# Power.net
KiCad netlist of a schematic drawn in Altium Designer
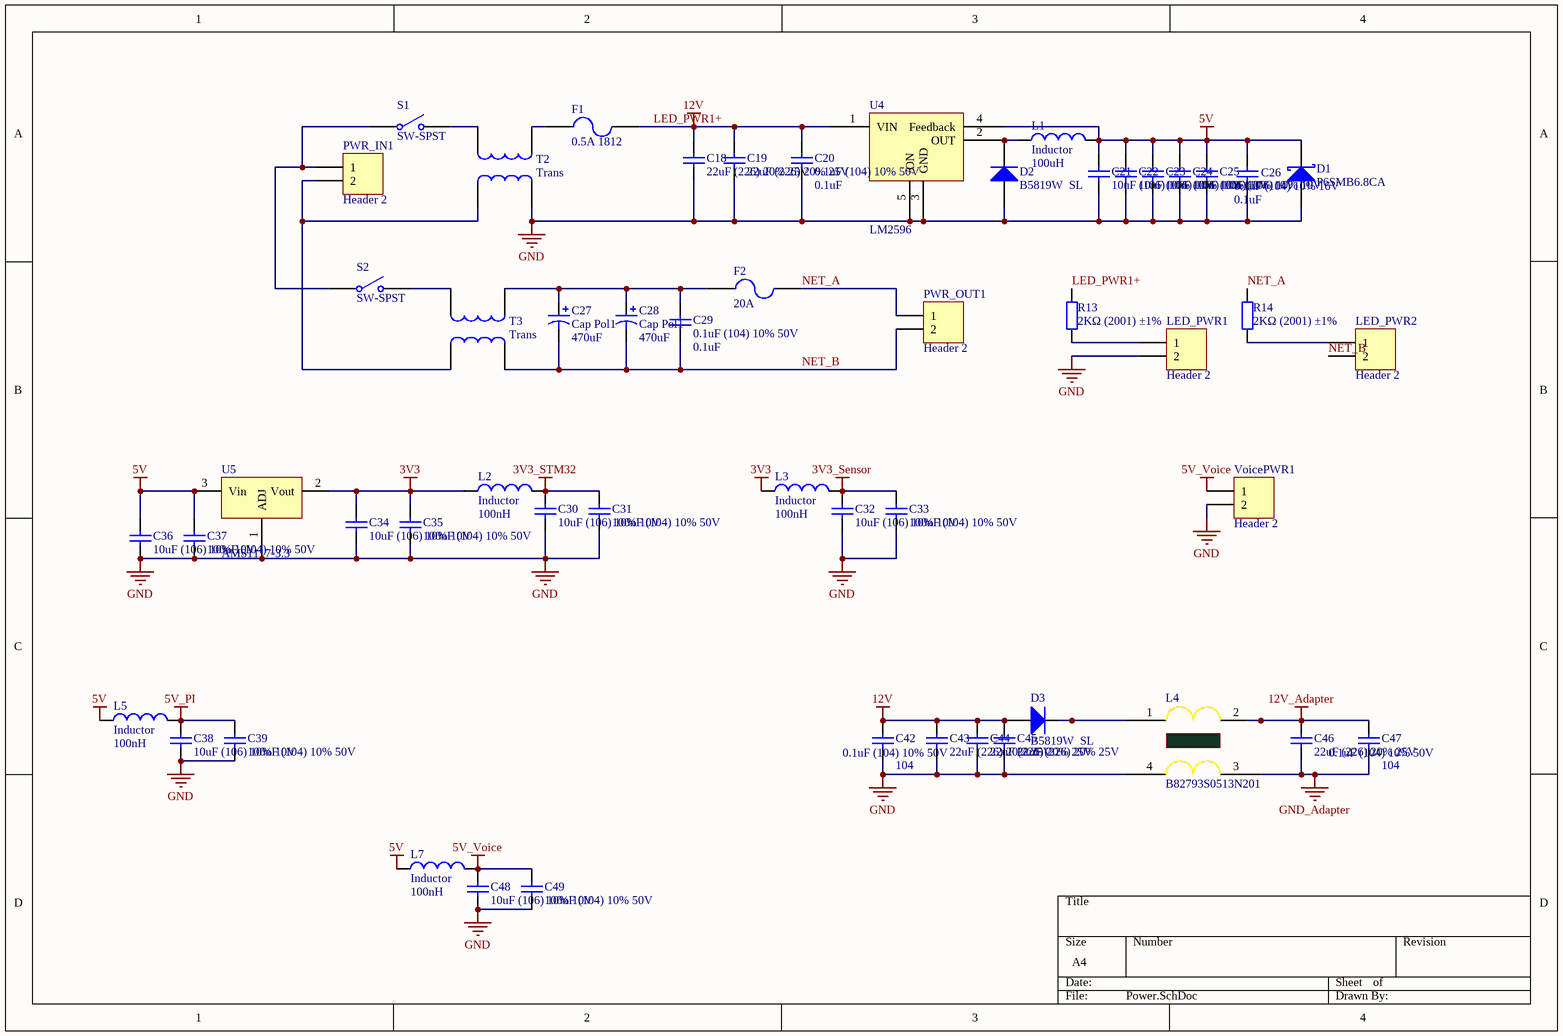
[diagram p0: Power.SchDoc]

(export (version "E")
  (design (tool "Eeschema 10.0.6"))
  (components
    (comp (ref "C18")
      (value "22uF (226) 20% 25V")
      (footprint "0805_C")
      (description "贴片电容")
      (libsource (lib "Miscellaneous Devices LC") (part "0805 22uF (226) 20% 25V"))
    )
    (comp (ref "C19")
      (value "22uF (226) 20% 25V")
      (footprint "0805_C")
      (description "贴片电容")
      (libsource (lib "Miscellaneous Devices LC") (part "0805 22uF (226) 20% 25V"))
    )
    (comp (ref "C20")
      (value "0.1uF (104) 10% 50V")
      (footprint "0805_C")
      (description "Capacitor")
      (fields (field (name "ALTIUM_VALUE") "0.1uF") (field (name "PUBLISHER") "Altium Limited"))
      (libsource (lib "Miscellaneous Devices") (part "Cap"))
    )
    (comp (ref "C21")
      (value "10uF (106) 10% 10V")
      (footprint "0603_C")
      (description "贴片电容")
      (libsource (lib "Miscellaneous Devices LC") (part "0603 10uF (106) 10% 10V"))
    )
    (comp (ref "C22")
      (value "10uF (106) 10% 10V")
      (footprint "0603_C")
      (description "贴片电容")
      (libsource (lib "Miscellaneous Devices LC") (part "0603 10uF (106) 10% 10V"))
    )
    (comp (ref "C23")
      (value "10uF (106) 10% 10V")
      (footprint "0603_C")
      (description "贴片电容")
      (libsource (lib "Miscellaneous Devices LC") (part "0603 10uF (106) 10% 10V"))
    )
    (comp (ref "C24")
      (value "10uF (106) 10% 10V")
      (footprint "0603_C")
      (description "贴片电容")
      (libsource (lib "Miscellaneous Devices LC") (part "0603 10uF (106) 10% 10V"))
    )
    (comp (ref "C25")
      (value "10uF (106) 10% 10V")
      (footprint "0603_C")
      (description "贴片电容")
      (libsource (lib "Miscellaneous Devices LC") (part "0603 10uF (106) 10% 10V"))
    )
    (comp (ref "C26")
      (value "0.1uF (104) 10% 16V")
      (footprint "0603_C")
      (description "Capacitor")
      (fields (field (name "ALTIUM_VALUE") "0.1uF") (field (name "PUBLISHER") "Altium Limited"))
      (libsource (lib "Miscellaneous Devices") (part "Cap"))
    )
    (comp (ref "C27")
      (value "Cap Pol1")
      (footprint "RB5-10.5")
      (description "Polarized Capacitor (Radial)")
      (fields (field (name "ALTIUM_VALUE") "470uF") (field (name "PUBLISHER") "Altium Limited"))
      (libsource (lib "Miscellaneous Devices") (part "Cap Pol1"))
    )
    (comp (ref "C28")
      (value "Cap Pol1")
      (footprint "RB5-10.5")
      (description "Polarized Capacitor (Radial)")
      (fields (field (name "ALTIUM_VALUE") "470uF") (field (name "PUBLISHER") "Altium Limited"))
      (libsource (lib "Miscellaneous Devices") (part "Cap Pol1"))
    )
    (comp (ref "C29")
      (value "0.1uF (104) 10% 50V")
      (footprint "0805_C")
      (description "Capacitor")
      (fields (field (name "ALTIUM_VALUE") "0.1uF") (field (name "PUBLISHER") "Altium Limited"))
      (libsource (lib "Miscellaneous Devices") (part "Cap"))
    )
    (comp (ref "C30")
      (value "10uF (106) 10% 10V")
      (footprint "0603_C")
      (description "贴片电容")
      (libsource (lib "Miscellaneous Devices LC") (part "0603 10uF (106) 10% 10V"))
    )
    (comp (ref "C31")
      (value "100nF (104) 10% 50V")
      (footprint "0603_C")
      (description "贴片电容")
      (libsource (lib "Miscellaneous Devices LC") (part "0603 100nF (104) 10% 50V"))
    )
    (comp (ref "C32")
      (value "10uF (106) 10% 10V")
      (footprint "0603_C")
      (description "贴片电容")
      (libsource (lib "Miscellaneous Devices LC") (part "0603 10uF (106) 10% 10V"))
    )
    (comp (ref "C33")
      (value "100nF (104) 10% 50V")
      (footprint "0603_C")
      (description "贴片电容")
      (libsource (lib "Miscellaneous Devices LC") (part "0603 100nF (104) 10% 50V"))
    )
    (comp (ref "C34")
      (value "10uF (106) 10% 10V")
      (footprint "0603_C")
      (description "贴片电容")
      (libsource (lib "Miscellaneous Devices LC") (part "0603 10uF (106) 10% 10V"))
    )
    (comp (ref "C35")
      (value "100nF (104) 10% 50V")
      (footprint "0603_C")
      (description "贴片电容")
      (libsource (lib "Miscellaneous Devices LC") (part "0603 100nF (104) 10% 50V"))
    )
    (comp (ref "C36")
      (value "10uF (106) 10% 10V")
      (footprint "0603_C")
      (description "贴片电容")
      (libsource (lib "Miscellaneous Devices LC") (part "0603 10uF (106) 10% 10V"))
    )
    (comp (ref "C37")
      (value "100nF (104) 10% 50V")
      (footprint "0603_C")
      (description "贴片电容")
      (libsource (lib "Miscellaneous Devices LC") (part "0603 100nF (104) 10% 50V"))
    )
    (comp (ref "C38")
      (value "10uF (106) 10% 10V")
      (footprint "0603_C")
      (description "贴片电容")
      (libsource (lib "Miscellaneous Devices LC") (part "0603 10uF (106) 10% 10V"))
    )
    (comp (ref "C39")
      (value "100nF (104) 10% 50V")
      (footprint "0603_C")
      (description "贴片电容")
      (libsource (lib "Miscellaneous Devices LC") (part "0603 100nF (104) 10% 50V"))
    )
    (comp (ref "C42")
      (value "0.1uF (104) 10% 50V")
      (footprint "0805_C")
      (description "Capacitor")
      (fields (field (name "ALTIUM_VALUE") "104") (field (name "PUBLISHER") "Altium Limited"))
      (libsource (lib "Miscellaneous Devices") (part "Cap"))
    )
    (comp (ref "C43")
      (value "22uF (226) 20% 25V")
      (footprint "0805_C")
      (description "贴片电容")
      (libsource (lib "Miscellaneous Devices LC") (part "0805 22uF (226) 20% 25V"))
    )
    (comp (ref "C44")
      (value "22uF (226) 20% 25V")
      (footprint "0805_C")
      (description "贴片电容")
      (libsource (lib "Miscellaneous Devices LC") (part "0805 22uF (226) 20% 25V"))
    )
    (comp (ref "C45")
      (value "22uF (226) 20% 25V")
      (footprint "0805_C")
      (description "贴片电容")
      (libsource (lib "Miscellaneous Devices LC") (part "0805 22uF (226) 20% 25V"))
    )
    (comp (ref "C46")
      (value "22uF (226) 20% 25V")
      (footprint "0805_C")
      (description "贴片电容")
      (libsource (lib "Miscellaneous Devices LC") (part "0805 22uF (226) 20% 25V"))
    )
    (comp (ref "C47")
      (value "0.1uF (104) 10% 50V")
      (footprint "0805_C")
      (description "Capacitor")
      (fields (field (name "ALTIUM_VALUE") "104") (field (name "PUBLISHER") "Altium Limited"))
      (libsource (lib "Miscellaneous Devices") (part "Cap"))
    )
    (comp (ref "C48")
      (value "10uF (106) 10% 10V")
      (footprint "0603_C")
      (description "贴片电容")
      (libsource (lib "Miscellaneous Devices LC") (part "0603 10uF (106) 10% 10V"))
    )
    (comp (ref "C49")
      (value "100nF (104) 10% 50V")
      (footprint "0603_C")
      (description "贴片电容")
      (libsource (lib "Miscellaneous Devices LC") (part "0603 100nF (104) 10% 50V"))
    )
    (comp (ref "D1")
      (value "P6SMB6.8CA")
      (footprint "SMB(DO-214AA)_S1")
      (description "Schottky Diode")
      (fields (field (name "PUBLISHER") "Altium Limited"))
      (libsource (lib "Miscellaneous Devices") (part "D Schottky"))
    )
    (comp (ref "D2")
      (value "B5819W  SL")
      (footprint "SOD-123")
      (description "肖特基二极管")
      (libsource (lib "Miscellaneous Devices LC") (part "SOD-123 B5819W  SL"))
    )
    (comp (ref "D3")
      (value "B5819W  SL")
      (footprint "SOD-123")
      (description "肖特基二极管")
      (libsource (lib "Miscellaneous Devices LC") (part "SOD-123 B5819W  SL"))
    )
    (comp (ref "F1")
      (value "0.5A 1812")
      (footprint "1812")
      (description "Fuse")
      (fields (field (name "PUBLISHER") "Altium Limited"))
      (libsource (lib "Miscellaneous Devices") (part "Fuse 2"))
    )
    (comp (ref "F2")
      (value "20A")
      (footprint "Fuse_Small")
      (description "Fuse")
      (fields (field (name "PUBLISHER") "Altium Limited"))
      (libsource (lib "Miscellaneous Devices") (part "Fuse 2"))
    )
    (comp (ref "L1")
      (value "Inductor")
      (footprint "L1050(10x10x4)")
      (fields (field (name "ALTIUM_VALUE") "100uH") (field (name "PUBLISHER") "Altium Limited"))
      (libsource (lib "Miscellaneous Devices") (part "Inductor"))
    )
    (comp (ref "L2")
      (value "Inductor")
      (footprint "0603_L")
      (fields (field (name "ALTIUM_VALUE") "100nH") (field (name "PUBLISHER") "Altium Limited"))
      (libsource (lib "Miscellaneous Devices") (part "Inductor"))
    )
    (comp (ref "L3")
      (value "Inductor")
      (footprint "0603_L")
      (fields (field (name "ALTIUM_VALUE") "100nH") (field (name "PUBLISHER") "Altium Limited"))
      (libsource (lib "Miscellaneous Devices") (part "Inductor"))
    )
    (comp (ref "L4")
      (value "B82793S0513N201")
      (footprint "B82793S0513N201_Yes")
      (libsource (lib "滤波器") (part "B82793S0513N201"))
    )
    (comp (ref "L5")
      (value "Inductor")
      (footprint "0603_L")
      (fields (field (name "ALTIUM_VALUE") "100nH") (field (name "PUBLISHER") "Altium Limited"))
      (libsource (lib "Miscellaneous Devices") (part "Inductor"))
    )
    (comp (ref "L7")
      (value "Inductor")
      (footprint "0603_L")
      (fields (field (name "ALTIUM_VALUE") "100nH") (field (name "PUBLISHER") "Altium Limited"))
      (libsource (lib "Miscellaneous Devices") (part "Inductor"))
    )
    (comp (ref "LED_PWR1")
      (value "Header 2")
      (footprint "XH2.54_2P")
      (description "Header, 2-Pin")
      (fields (field (name "PUBLISHER") "Altium Limited"))
      (libsource (lib "Miscellaneous Connectors") (part "Header 2"))
    )
    (comp (ref "LED_PWR2")
      (value "Header 2")
      (footprint "XH2.54_2P")
      (description "Header, 2-Pin")
      (fields (field (name "PUBLISHER") "Altium Limited"))
      (libsource (lib "Miscellaneous Connectors") (part "Header 2"))
    )
    (comp (ref "PWR_IN1")
      (value "Header 2")
      (footprint "T型口")
      (description "Header, 2-Pin")
      (fields (field (name "PUBLISHER") "Altium Limited"))
      (libsource (lib "Miscellaneous Connectors") (part "Header 2"))
    )
    (comp (ref "PWR_OUT1")
      (value "Header 2")
      (footprint "T型口")
      (description "Header, 2-Pin")
      (fields (field (name "PUBLISHER") "Altium Limited"))
      (libsource (lib "Miscellaneous Connectors") (part "Header 2"))
    )
    (comp (ref "R13")
      (value "2KΩ (2001) ±1%")
      (footprint "LC-0603_R")
      (description "贴片电阻")
      (libsource (lib "Miscellaneous Devices LC") (part "0603 2KΩ (2001) 1%"))
    )
    (comp (ref "R14")
      (value "2KΩ (2001) ±1%")
      (footprint "LC-0603_R")
      (description "贴片电阻")
      (libsource (lib "Miscellaneous Devices LC") (part "0603 2KΩ (2001) 1%"))
    )
    (comp (ref "S1")
      (value "SW-SPST")
      (footprint "XH2.54_2P")
      (description "Single-Pole, Single-Throw Switch")
      (fields (field (name "PUBLISHER") "Altium Limited"))
      (libsource (lib "Miscellaneous Devices") (part "SW-SPST"))
    )
    (comp (ref "S2")
      (value "SW-SPST")
      (footprint "T型口")
      (description "Single-Pole, Single-Throw Switch")
      (fields (field (name "PUBLISHER") "Altium Limited"))
      (libsource (lib "Miscellaneous Devices") (part "SW-SPST"))
    )
    (comp (ref "T2")
      (value "Trans")
      (footprint "UU9.8")
      (description "Transformer")
      (fields (field (name "PUBLISHER") "Altium Limited"))
      (libsource (lib "Miscellaneous Devices") (part "Trans"))
    )
    (comp (ref "T3")
      (value "Trans")
      (footprint "20A共模电感")
      (description "Transformer")
      (fields (field (name "PUBLISHER") "Altium Limited"))
      (libsource (lib "Miscellaneous Devices") (part "Trans"))
    )
    (comp (ref "U4")
      (value "LM2596")
      (footprint "TO-263-5")
      (libsource (lib "STM32F103C8T6(原理图库)") (part "LM2576"))
    )
    (comp (ref "U5")
      (value "AMS1117-3.3")
      (footprint "SOT-223")
      (description "3-Terminal Adjustable Positive Voltage Regulator")
      (libsource (lib "稳压器件") (part "LM317"))
    )
    (comp (ref "VoicePWR1")
      (value "Header 2")
      (footprint "XH2.54_2P")
      (description "Header, 2-Pin")
      (fields (field (name "PUBLISHER") "Altium Limited"))
      (libsource (lib "Miscellaneous Connectors") (part "Header 2"))
    )
  )
  (nets
    (net (code "1") (name "/NET_A") (class "Default")
      (node (ref "F2") (pin "2") (pinfunction "2_2") (pintype "passive"))
      (node (ref "PWR_OUT1") (pin "1") (pinfunction "1_1") (pintype "passive"))
      (node (ref "R14") (pin "1") (pinfunction "1_1") (pintype "passive"))
    )
    (net (code "2") (name "/NET_B") (class "Default")
      (node (ref "C27") (pin "2") (pinfunction "2_2") (pintype "passive"))
      (node (ref "C28") (pin "2") (pinfunction "2_2") (pintype "passive"))
      (node (ref "C29") (pin "1") (pinfunction "1_1") (pintype "passive"))
      (node (ref "LED_PWR2") (pin "2") (pinfunction "2_2") (pintype "passive"))
      (node (ref "PWR_OUT1") (pin "2") (pinfunction "2_2") (pintype "passive"))
      (node (ref "T3") (pin "2") (pinfunction "2_2") (pintype "passive"))
    )
    (net (code "3") (name "3V3") (class "Default")
      (node (ref "C34") (pin "2") (pinfunction "2_2") (pintype "passive"))
      (node (ref "C35") (pin "2") (pinfunction "2_2") (pintype "passive"))
      (node (ref "L2") (pin "1") (pinfunction "1_1") (pintype "passive"))
      (node (ref "L3") (pin "1") (pinfunction "1_1") (pintype "passive"))
      (node (ref "U5") (pin "2") (pinfunction "Vout_2") (pintype "passive"))
    )
    (net (code "4") (name "3V3_STM32") (class "Default")
      (node (ref "C30") (pin "2") (pinfunction "2_2") (pintype "passive"))
      (node (ref "C31") (pin "2") (pinfunction "2_2") (pintype "passive"))
      (node (ref "L2") (pin "2") (pinfunction "2_2") (pintype "passive"))
    )
    (net (code "5") (name "3V3_Sensor") (class "Default")
      (node (ref "C32") (pin "2") (pinfunction "2_2") (pintype "passive"))
      (node (ref "C33") (pin "2") (pinfunction "2_2") (pintype "passive"))
      (node (ref "L3") (pin "2") (pinfunction "2_2") (pintype "passive"))
    )
    (net (code "6") (name "5V") (class "Default")
      (node (ref "C21") (pin "2") (pinfunction "2_2") (pintype "passive"))
      (node (ref "C22") (pin "2") (pinfunction "2_2") (pintype "passive"))
      (node (ref "C23") (pin "2") (pinfunction "2_2") (pintype "passive"))
      (node (ref "C24") (pin "2") (pinfunction "2_2") (pintype "passive"))
      (node (ref "C25") (pin "2") (pinfunction "2_2") (pintype "passive"))
      (node (ref "C26") (pin "2") (pinfunction "2_2") (pintype "passive"))
      (node (ref "C36") (pin "2") (pinfunction "2_2") (pintype "passive"))
      (node (ref "C37") (pin "2") (pinfunction "2_2") (pintype "passive"))
      (node (ref "D1") (pin "2") (pinfunction "K_2") (pintype "passive"))
      (node (ref "L1") (pin "2") (pinfunction "2_2") (pintype "passive"))
      (node (ref "L5") (pin "1") (pinfunction "1_1") (pintype "passive"))
      (node (ref "L7") (pin "1") (pinfunction "1_1") (pintype "passive"))
      (node (ref "U4") (pin "4") (pinfunction "Feedback_4") (pintype "passive"))
      (node (ref "U5") (pin "3") (pinfunction "Vin_3") (pintype "passive"))
    )
    (net (code "7") (name "5V_PI") (class "Default")
      (node (ref "C38") (pin "2") (pinfunction "2_2") (pintype "passive"))
      (node (ref "C39") (pin "2") (pinfunction "2_2") (pintype "passive"))
      (node (ref "L5") (pin "2") (pinfunction "2_2") (pintype "passive"))
    )
    (net (code "8") (name "5V_Voice") (class "Default")
      (node (ref "C48") (pin "2") (pinfunction "2_2") (pintype "passive"))
      (node (ref "C49") (pin "2") (pinfunction "2_2") (pintype "passive"))
      (node (ref "L7") (pin "2") (pinfunction "2_2") (pintype "passive"))
      (node (ref "VoicePWR1") (pin "1") (pinfunction "1_1") (pintype "passive"))
    )
    (net (code "9") (name "12V") (class "Default")
      (node (ref "C18") (pin "2") (pinfunction "2_2") (pintype "passive"))
      (node (ref "C19") (pin "2") (pinfunction "2_2") (pintype "passive"))
      (node (ref "C20") (pin "2") (pinfunction "2_2") (pintype "passive"))
      (node (ref "C42") (pin "2") (pinfunction "2_2") (pintype "passive"))
      (node (ref "C43") (pin "2") (pinfunction "2_2") (pintype "passive"))
      (node (ref "C44") (pin "2") (pinfunction "2_2") (pintype "passive"))
      (node (ref "C45") (pin "2") (pinfunction "2_2") (pintype "passive"))
      (node (ref "D3") (pin "1") (pinfunction "A_1") (pintype "passive"))
      (node (ref "F1") (pin "2") (pinfunction "2_2") (pintype "passive"))
      (node (ref "R13") (pin "1") (pinfunction "1_1") (pintype "passive"))
      (node (ref "U4") (pin "1") (pinfunction "VIN_1") (pintype "passive"))
    )
    (net (code "10") (name "12V_Adapter") (class "Default")
      (node (ref "C46") (pin "2") (pinfunction "2_2") (pintype "passive"))
      (node (ref "C47") (pin "2") (pinfunction "2_2") (pintype "passive"))
      (node (ref "L4") (pin "2") (pinfunction "2_2") (pintype "passive"))
    )
    (net (code "11") (name "GND") (class "Default")
      (node (ref "C18") (pin "1") (pinfunction "1_1") (pintype "passive"))
      (node (ref "C19") (pin "1") (pinfunction "1_1") (pintype "passive"))
      (node (ref "C20") (pin "1") (pinfunction "1_1") (pintype "passive"))
      (node (ref "C21") (pin "1") (pinfunction "1_1") (pintype "passive"))
      (node (ref "C22") (pin "1") (pinfunction "1_1") (pintype "passive"))
      (node (ref "C23") (pin "1") (pinfunction "1_1") (pintype "passive"))
      (node (ref "C24") (pin "1") (pinfunction "1_1") (pintype "passive"))
      (node (ref "C25") (pin "1") (pinfunction "1_1") (pintype "passive"))
      (node (ref "C26") (pin "1") (pinfunction "1_1") (pintype "passive"))
      (node (ref "C30") (pin "1") (pinfunction "1_1") (pintype "passive"))
      (node (ref "C31") (pin "1") (pinfunction "1_1") (pintype "passive"))
      (node (ref "C32") (pin "1") (pinfunction "1_1") (pintype "passive"))
      (node (ref "C33") (pin "1") (pinfunction "1_1") (pintype "passive"))
      (node (ref "C34") (pin "1") (pinfunction "1_1") (pintype "passive"))
      (node (ref "C35") (pin "1") (pinfunction "1_1") (pintype "passive"))
      (node (ref "C36") (pin "1") (pinfunction "1_1") (pintype "passive"))
      (node (ref "C37") (pin "1") (pinfunction "1_1") (pintype "passive"))
      (node (ref "C38") (pin "1") (pinfunction "1_1") (pintype "passive"))
      (node (ref "C39") (pin "1") (pinfunction "1_1") (pintype "passive"))
      (node (ref "C42") (pin "1") (pinfunction "1_1") (pintype "passive"))
      (node (ref "C43") (pin "1") (pinfunction "1_1") (pintype "passive"))
      (node (ref "C44") (pin "1") (pinfunction "1_1") (pintype "passive"))
      (node (ref "C45") (pin "1") (pinfunction "1_1") (pintype "passive"))
      (node (ref "C48") (pin "1") (pinfunction "1_1") (pintype "passive"))
      (node (ref "C49") (pin "1") (pinfunction "1_1") (pintype "passive"))
      (node (ref "D1") (pin "1") (pinfunction "A_1") (pintype "passive"))
      (node (ref "D2") (pin "1") (pinfunction "A_1") (pintype "passive"))
      (node (ref "L4") (pin "4") (pinfunction "4_4") (pintype "passive"))
      (node (ref "LED_PWR1") (pin "2") (pinfunction "2_2") (pintype "passive"))
      (node (ref "T2") (pin "2") (pinfunction "2_2") (pintype "passive"))
      (node (ref "U4") (pin "3") (pinfunction "GND_3") (pintype "passive"))
      (node (ref "U4") (pin "5") (pinfunction "/ON_5") (pintype "passive"))
      (node (ref "U5") (pin "1") (pinfunction "ADJ_1") (pintype "passive"))
      (node (ref "VoicePWR1") (pin "2") (pinfunction "2_2") (pintype "passive"))
    )
    (net (code "12") (name "GND_Adapter") (class "Default")
      (node (ref "C46") (pin "1") (pinfunction "1_1") (pintype "passive"))
      (node (ref "C47") (pin "1") (pinfunction "1_1") (pintype "passive"))
      (node (ref "L4") (pin "3") (pinfunction "3_3") (pintype "passive"))
    )
    (net (code "13") (name "Net-(C27-Pad1)") (class "Default")
      (node (ref "C27") (pin "1") (pinfunction "1_1") (pintype "passive"))
      (node (ref "C28") (pin "1") (pinfunction "1_1") (pintype "passive"))
      (node (ref "C29") (pin "2") (pinfunction "2_2") (pintype "passive"))
      (node (ref "F2") (pin "1") (pinfunction "1_1") (pintype "passive"))
      (node (ref "T3") (pin "4") (pinfunction "4_4") (pintype "passive"))
    )
    (net (code "14") (name "Net-(D2-K)") (class "Default")
      (node (ref "D2") (pin "2") (pinfunction "K_2") (pintype "passive"))
      (node (ref "L1") (pin "1") (pinfunction "1_1") (pintype "passive"))
      (node (ref "U4") (pin "2") (pinfunction "OUT_2") (pintype "passive"))
    )
    (net (code "15") (name "Net-(D3-K)") (class "Default")
      (node (ref "D3") (pin "2") (pinfunction "K_2") (pintype "passive"))
      (node (ref "L4") (pin "1") (pinfunction "1_1") (pintype "passive"))
    )
    (net (code "16") (name "Net-(F1-Pad1)") (class "Default")
      (node (ref "F1") (pin "1") (pinfunction "1_1") (pintype "passive"))
      (node (ref "T2") (pin "4") (pinfunction "4_4") (pintype "passive"))
    )
    (net (code "17") (name "Net-(LED_PWR1-Pad1)") (class "Default")
      (node (ref "LED_PWR1") (pin "1") (pinfunction "1_1") (pintype "passive"))
      (node (ref "R13") (pin "2") (pinfunction "2_2") (pintype "passive"))
    )
    (net (code "18") (name "Net-(LED_PWR2-Pad1)") (class "Default")
      (node (ref "LED_PWR2") (pin "1") (pinfunction "1_1") (pintype "passive"))
      (node (ref "R14") (pin "2") (pinfunction "2_2") (pintype "passive"))
    )
    (net (code "19") (name "Net-(PWR_IN1-Pad2)") (class "Default")
      (node (ref "PWR_IN1") (pin "2") (pinfunction "2_2") (pintype "passive"))
      (node (ref "T2") (pin "1") (pinfunction "1_1") (pintype "passive"))
      (node (ref "T3") (pin "1") (pinfunction "1_1") (pintype "passive"))
    )
    (net (code "20") (name "Net-(S1-COMMON)") (class "Default")
      (node (ref "PWR_IN1") (pin "1") (pinfunction "1_1") (pintype "passive"))
      (node (ref "S1") (pin "1") (pinfunction "COMMON_1") (pintype "passive"))
      (node (ref "S2") (pin "1") (pinfunction "COMMON_1") (pintype "passive"))
    )
    (net (code "21") (name "Net-(S1-NO)") (class "Default")
      (node (ref "S1") (pin "2") (pinfunction "NO_2") (pintype "passive"))
      (node (ref "T2") (pin "3") (pinfunction "3_3") (pintype "passive"))
    )
    (net (code "22") (name "Net-(S2-NO)") (class "Default")
      (node (ref "S2") (pin "2") (pinfunction "NO_2") (pintype "passive"))
      (node (ref "T3") (pin "3") (pinfunction "3_3") (pintype "passive"))
    )
  )
)
